# SCH_HDMI_GPIO.net
KiCad netlist of a schematic drawn in Altium Designer
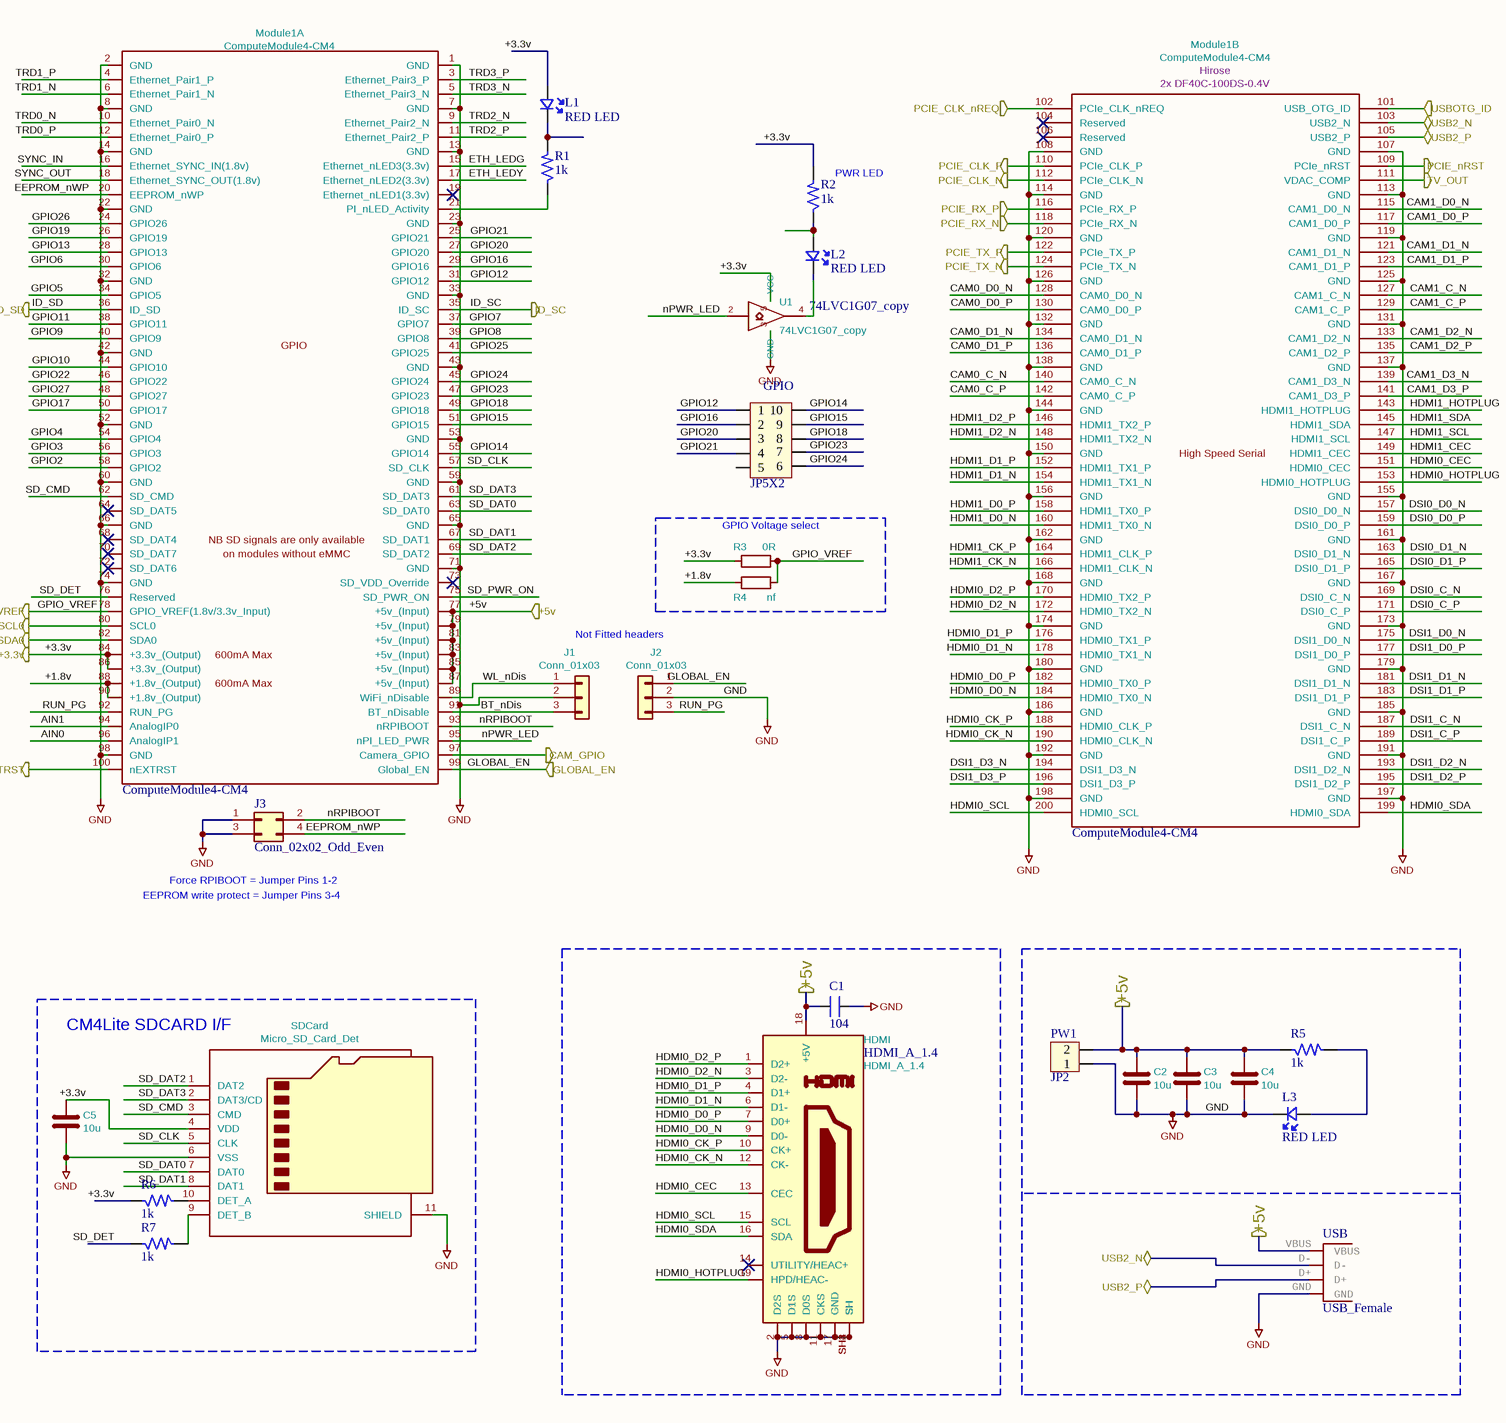
[diagram p0: SCH_HDMI_GPIO.SchDoc]

(export (version "E")
  (design (tool "Eeschema 10.0.6"))
  (components
    (comp (ref "C1")
      (value "104")
      (footprint "SM-CAP-0805")
      (fields (field (name "DESIGNED BY") "VanDungEvn"))
      (libsource (lib "QD_Lib_Altum") (part "CN"))
    )
    (comp (ref "C2") (value "10u") (footprint "C_0805_2012Metric") (libsource (lib "Device") (part "C")))
    (comp (ref "C3") (value "10u") (footprint "C_0805_2012Metric") (libsource (lib "Device") (part "C")))
    (comp (ref "C4") (value "10u") (footprint "C_0805_2012Metric") (libsource (lib "Device") (part "C")))
    (comp (ref "C5") (value "10u") (footprint "C_0805_2012Metric") (libsource (lib "Device") (part "C")))
    (comp (ref "GPIO") (value "JP5X2") (footprint "JP5X2") (libsource (lib "QD_Lib_Altum") (part "JP5X2")))
    (comp (ref "HDMI")
      (value "HDMI_A_1.4")
      (footprint "HDMI")
      (fields (field (name "ALTIUM_VALUE") "HDMI_A_1.4"))
      (libsource (lib "CM4IO") (part "HDMI_A_1.4"))
    )
    (comp (ref "J1")
      (value "Conn_01x03")
      (footprint "PinHeader_1x03_P2.54mm_Vertical")
      (libsource (lib "Connector_Generic") (part "Conn_01x03"))
    )
    (comp (ref "J2")
      (value "Conn_01x03")
      (footprint "PinHeader_1x03_P2.54mm_Vertical")
      (libsource (lib "") (part "Conn_01x03_1"))
    )
    (comp (ref "J3")
      (value "Conn_02x02_Odd_Even")
      (footprint "CON2x2")
      (libsource (lib "CM4_GPIO") (part "Conn_02x02_Odd_Even"))
    )
    (comp (ref "L1")
      (value "RED LED")
      (footprint "LED_0805")
      (description "Red 621nm LED Indication - Discrete 2V 0805 (2012 Metric)")
      (fields
        (field (name "MANUFACTURER") "Lite-On Inc.")
        (field (name "MANUFACTURER PART NUMBER") "LTST-C170EKT")
      )
      (libsource (lib "QD_Lib_Altum") (part "LED-RED_10mA-0805"))
    )
    (comp (ref "L2")
      (value "RED LED")
      (footprint "LED_0805")
      (description "Red 621nm LED Indication - Discrete 2V 0805 (2012 Metric)")
      (fields
        (field (name "MANUFACTURER") "Lite-On Inc.")
        (field (name "MANUFACTURER PART NUMBER") "LTST-C170EKT")
      )
      (libsource (lib "QD_Lib_Altum") (part "LED-RED_10mA-0805"))
    )
    (comp (ref "L3")
      (value "RED LED")
      (footprint "LED_0805")
      (description "Red 621nm LED Indication - Discrete 2V 0805 (2012 Metric)")
      (fields
        (field (name "MANUFACTURER") "Lite-On Inc.")
        (field (name "MANUFACTURER PART NUMBER") "LTST-C170EKT")
      )
      (libsource (lib "QD_Lib_Altum") (part "LED-RED_10mA-0805"))
    )
    (comp (ref "Module1")
      (value "ComputeModule4-CM4")
      (footprint "Raspberry-Pi-4-Compute-Module")
      (fields
        (field (name "ALTIUM_VALUE") "ComputeModule4-CM4")
        (field (name "FIELD4") "Hirose")
        (field (name "FIELD5") "2x DF40C-100DS-0.4V")
      )
      (libsource (lib "CM4IO") (part "ComputeModule4-CM4"))
    )
    (comp (ref "PW1")
      (value "JP2")
      (footprint "CON2")
      (description "Connector 2")
      (libsource (lib "QD_Lib_Altum") (part "Con2"))
    )
    (comp (ref "R1")
      (value "1k")
      (footprint "SM-RES-1206")
      (description "Resistor 1/4W")
      (libsource (lib "QD_Lib_Altum") (part "R"))
    )
    (comp (ref "R2")
      (value "1k")
      (footprint "SM-RES-1206")
      (description "Resistor 1/4W")
      (libsource (lib "QD_Lib_Altum") (part "R"))
    )
    (comp (ref "R3")
      (value "0R")
      (footprint "R_0805_2012Metric_Pad1.15x1.40mm_HandSolder")
      (libsource (lib "Device") (part "R"))
    )
    (comp (ref "R4")
      (value "nf")
      (footprint "R_0805_2012Metric_Pad1.15x1.40mm_HandSolder")
      (libsource (lib "Device") (part "R"))
    )
    (comp (ref "R5")
      (value "1k")
      (footprint "SM-RES-1206")
      (description "Resistor 1/4W")
      (libsource (lib "QD_Lib_Altum") (part "R"))
    )
    (comp (ref "R6")
      (value "1k")
      (footprint "SM-RES-1206")
      (description "Resistor 1/4W")
      (libsource (lib "QD_Lib_Altum") (part "R"))
    )
    (comp (ref "R7")
      (value "1k")
      (footprint "SM-RES-1206")
      (description "Resistor 1/4W")
      (libsource (lib "QD_Lib_Altum") (part "R"))
    )
    (comp (ref "SDCard")
      (value "Micro_SD_Card_Det")
      (footprint "SDCARD_MOLEX_503398-1892")
      (libsource (lib "Connector") (part "Micro_SD_Card_Det"))
    )
    (comp (ref "U1")
      (value "74LVC1G07_copy")
      (footprint "SOT-353_SC-70-5")
      (fields (field (name "ALTIUM_VALUE") "74LVC1G07_copy"))
      (libsource (lib "CM4IO") (part "74LVC1G07_copy"))
    )
    (comp (ref "USB")
      (value "USB_Female")
      (footprint "USB_Female")
      (libsource (lib "USB2-HUB") (part "USB_Female"))
    )
  )
  (nets
    (net (code "1") (name "/+1.8v") (class "Default")
      (node (ref "Module1") (pin "88") (pinfunction "+1.8v_(Output)_88") (pintype "passive"))
      (node (ref "Module1") (pin "90") (pinfunction "+1.8v_(Output)_90") (pintype "passive"))
      (node (ref "R4") (pin "1") (pinfunction "1_1") (pintype "passive"))
    )
    (net (code "2") (name "/+3.3v") (class "Default")
      (node (ref "C5") (pin "1") (pinfunction "1_1") (pintype "passive"))
      (node (ref "L1") (pin "A") (pinfunction "A_A") (pintype "passive"))
      (node (ref "Module1") (pin "84") (pinfunction "+3.3v_(Output)_84") (pintype "passive"))
      (node (ref "Module1") (pin "86") (pinfunction "+3.3v_(Output)_86") (pintype "passive"))
      (node (ref "R2") (pin "2") (pinfunction "2_2") (pintype "passive"))
      (node (ref "R3") (pin "1") (pinfunction "1_1") (pintype "passive"))
      (node (ref "R6") (pin "1") (pinfunction "1_1") (pintype "passive"))
      (node (ref "SDCard") (pin "4") (pinfunction "VDD_4") (pintype "passive"))
      (node (ref "U1") (pin "5") (pinfunction "VCC_5") (pintype "passive"))
    )
    (net (code "3") (name "/+5v") (class "Default")
      (node (ref "C1") (pin "1") (pinfunction "1_1") (pintype "passive"))
      (node (ref "C2") (pin "1") (pinfunction "1_1") (pintype "passive"))
      (node (ref "C3") (pin "1") (pinfunction "1_1") (pintype "passive"))
      (node (ref "C4") (pin "1") (pinfunction "1_1") (pintype "passive"))
      (node (ref "HDMI") (pin "18") (pinfunction "+5V_18") (pintype "passive"))
      (node (ref "Module1") (pin "77") (pinfunction "+5v_(Input)_77") (pintype "passive"))
      (node (ref "Module1") (pin "79") (pinfunction "+5v_(Input)_79") (pintype "passive"))
      (node (ref "Module1") (pin "81") (pinfunction "+5v_(Input)_81") (pintype "passive"))
      (node (ref "Module1") (pin "83") (pinfunction "+5v_(Input)_83") (pintype "passive"))
      (node (ref "Module1") (pin "85") (pinfunction "+5v_(Input)_85") (pintype "passive"))
      (node (ref "Module1") (pin "87") (pinfunction "+5v_(Input)_87") (pintype "passive"))
      (node (ref "PW1") (pin "2") (pinfunction "2_2") (pintype "passive"))
      (node (ref "R5") (pin "1") (pinfunction "1_1") (pintype "passive"))
      (node (ref "USB") (pin "VBUS") (pinfunction "VBUS_VBUS") (pintype "bidirectional"))
    )
    (net (code "4") (name "/AIN0") (class "Default")
      (node (ref "Module1") (pin "96") (pinfunction "AnalogIP1_96") (pintype "passive"))
    )
    (net (code "5") (name "/AIN1") (class "Default")
      (node (ref "Module1") (pin "94") (pinfunction "AnalogIP0_94") (pintype "passive"))
    )
    (net (code "6") (name "/BT_nDis") (class "Default")
      (node (ref "J1") (pin "3") (pinfunction "Pin_3_3") (pintype "passive"))
      (node (ref "Module1") (pin "91") (pinfunction "BT_nDisable_91") (pintype "passive"))
    )
    (net (code "7") (name "/CAM0_C_N") (class "Default")
      (node (ref "Module1") (pin "140") (pinfunction "CAM0_C_N_140") (pintype "passive"))
    )
    (net (code "8") (name "/CAM0_C_P") (class "Default")
      (node (ref "Module1") (pin "142") (pinfunction "CAM0_C_P_142") (pintype "passive"))
    )
    (net (code "9") (name "/CAM0_D0_N") (class "Default")
      (node (ref "Module1") (pin "128") (pinfunction "CAM0_D0_N_128") (pintype "passive"))
    )
    (net (code "10") (name "/CAM0_D0_P") (class "Default")
      (node (ref "Module1") (pin "130") (pinfunction "CAM0_D0_P_130") (pintype "passive"))
    )
    (net (code "11") (name "/CAM0_D1_N") (class "Default")
      (node (ref "Module1") (pin "134") (pinfunction "CAM0_D1_N_134") (pintype "passive"))
    )
    (net (code "12") (name "/CAM0_D1_P") (class "Default")
      (node (ref "Module1") (pin "136") (pinfunction "CAM0_D1_P_136") (pintype "passive"))
    )
    (net (code "13") (name "/CAM1_C_N") (class "Default")
      (node (ref "Module1") (pin "127") (pinfunction "CAM1_C_N_127") (pintype "passive"))
    )
    (net (code "14") (name "/CAM1_C_P") (class "Default")
      (node (ref "Module1") (pin "129") (pinfunction "CAM1_C_P_129") (pintype "passive"))
    )
    (net (code "15") (name "/CAM1_D0_N") (class "Default")
      (node (ref "Module1") (pin "115") (pinfunction "CAM1_D0_N_115") (pintype "passive"))
    )
    (net (code "16") (name "/CAM1_D0_P") (class "Default")
      (node (ref "Module1") (pin "117") (pinfunction "CAM1_D0_P_117") (pintype "passive"))
    )
    (net (code "17") (name "/CAM1_D1_N") (class "Default")
      (node (ref "Module1") (pin "121") (pinfunction "CAM1_D1_N_121") (pintype "passive"))
    )
    (net (code "18") (name "/CAM1_D1_P") (class "Default")
      (node (ref "Module1") (pin "123") (pinfunction "CAM1_D1_P_123") (pintype "passive"))
    )
    (net (code "19") (name "/CAM1_D2_N") (class "Default")
      (node (ref "Module1") (pin "133") (pinfunction "CAM1_D2_N_133") (pintype "passive"))
    )
    (net (code "20") (name "/CAM1_D2_P") (class "Default")
      (node (ref "Module1") (pin "135") (pinfunction "CAM1_D2_P_135") (pintype "passive"))
    )
    (net (code "21") (name "/CAM1_D3_N") (class "Default")
      (node (ref "Module1") (pin "139") (pinfunction "CAM1_D3_N_139") (pintype "passive"))
    )
    (net (code "22") (name "/CAM1_D3_P") (class "Default")
      (node (ref "Module1") (pin "141") (pinfunction "CAM1_D3_P_141") (pintype "passive"))
    )
    (net (code "23") (name "/CAM_GPIO") (class "Default")
      (node (ref "Module1") (pin "97") (pinfunction "Camera_GPIO_97") (pintype "passive"))
    )
    (net (code "24") (name "/DSI0_C_N") (class "Default")
      (node (ref "Module1") (pin "169") (pinfunction "DSI0_C_N_169") (pintype "passive"))
    )
    (net (code "25") (name "/DSI0_C_P") (class "Default")
      (node (ref "Module1") (pin "171") (pinfunction "DSI0_C_P_171") (pintype "passive"))
    )
    (net (code "26") (name "/DSI0_D0_N") (class "Default")
      (node (ref "Module1") (pin "157") (pinfunction "DSI0_D0_N_157") (pintype "passive"))
    )
    (net (code "27") (name "/DSI0_D0_P") (class "Default")
      (node (ref "Module1") (pin "159") (pinfunction "DSI0_D0_P_159") (pintype "passive"))
    )
    (net (code "28") (name "/DSI0_D1_N") (class "Default")
      (node (ref "Module1") (pin "163") (pinfunction "DSI0_D1_N_163") (pintype "passive"))
    )
    (net (code "29") (name "/DSI0_D1_P") (class "Default")
      (node (ref "Module1") (pin "165") (pinfunction "DSI0_D1_P_165") (pintype "passive"))
    )
    (net (code "30") (name "/DSI1_C_N") (class "Default")
      (node (ref "Module1") (pin "187") (pinfunction "DSI1_C_N_187") (pintype "passive"))
    )
    (net (code "31") (name "/DSI1_C_P") (class "Default")
      (node (ref "Module1") (pin "189") (pinfunction "DSI1_C_P_189") (pintype "passive"))
    )
    (net (code "32") (name "/DSI1_D0_N") (class "Default")
      (node (ref "Module1") (pin "175") (pinfunction "DSI1_D0_N_175") (pintype "passive"))
    )
    (net (code "33") (name "/DSI1_D0_P") (class "Default")
      (node (ref "Module1") (pin "177") (pinfunction "DSI1_D0_P_177") (pintype "passive"))
    )
    (net (code "34") (name "/DSI1_D1_N") (class "Default")
      (node (ref "Module1") (pin "181") (pinfunction "DSI1_D1_N_181") (pintype "passive"))
    )
    (net (code "35") (name "/DSI1_D1_P") (class "Default")
      (node (ref "Module1") (pin "183") (pinfunction "DSI1_D1_P_183") (pintype "passive"))
    )
    (net (code "36") (name "/DSI1_D2_N") (class "Default")
      (node (ref "Module1") (pin "193") (pinfunction "DSI1_D2_N_193") (pintype "passive"))
    )
    (net (code "37") (name "/DSI1_D2_P") (class "Default")
      (node (ref "Module1") (pin "195") (pinfunction "DSI1_D2_P_195") (pintype "passive"))
    )
    (net (code "38") (name "/DSI1_D3_N") (class "Default")
      (node (ref "Module1") (pin "194") (pinfunction "DSI1_D3_N_194") (pintype "passive"))
    )
    (net (code "39") (name "/DSI1_D3_P") (class "Default")
      (node (ref "Module1") (pin "196") (pinfunction "DSI1_D3_P_196") (pintype "passive"))
    )
    (net (code "40") (name "/EEPROM_nWP") (class "Default")
      (node (ref "J3") (pin "4") (pinfunction "Pin_4_4") (pintype "passive"))
      (node (ref "Module1") (pin "20") (pinfunction "EEPROM_nWP_20") (pintype "passive"))
    )
    (net (code "41") (name "/ETH_LEDG") (class "Default")
      (node (ref "Module1") (pin "15") (pinfunction "Ethernet_nLED3(3.3v)_15") (pintype "passive"))
    )
    (net (code "42") (name "/ETH_LEDY") (class "Default")
      (node (ref "Module1") (pin "17") (pinfunction "Ethernet_nLED2(3.3v)_17") (pintype "passive"))
    )
    (net (code "43") (name "/GLOBAL_EN") (class "Default")
      (node (ref "J2") (pin "1") (pinfunction "Pin_1_1") (pintype "passive"))
      (node (ref "Module1") (pin "99") (pinfunction "Global_EN_99") (pintype "passive"))
    )
    (net (code "44") (name "/GPIO2") (class "Default")
      (node (ref "Module1") (pin "58") (pinfunction "GPIO2_58") (pintype "passive"))
    )
    (net (code "45") (name "/GPIO3") (class "Default")
      (node (ref "Module1") (pin "56") (pinfunction "GPIO3_56") (pintype "passive"))
    )
    (net (code "46") (name "/GPIO4") (class "Default")
      (node (ref "Module1") (pin "54") (pinfunction "GPIO4_54") (pintype "passive"))
    )
    (net (code "47") (name "/GPIO5") (class "Default")
      (node (ref "Module1") (pin "34") (pinfunction "GPIO5_34") (pintype "passive"))
    )
    (net (code "48") (name "/GPIO6") (class "Default")
      (node (ref "Module1") (pin "30") (pinfunction "GPIO6_30") (pintype "passive"))
    )
    (net (code "49") (name "/GPIO7") (class "Default")
      (node (ref "Module1") (pin "37") (pinfunction "GPIO7_37") (pintype "passive"))
    )
    (net (code "50") (name "/GPIO8") (class "Default")
      (node (ref "Module1") (pin "39") (pinfunction "GPIO8_39") (pintype "passive"))
    )
    (net (code "51") (name "/GPIO9") (class "Default")
      (node (ref "Module1") (pin "40") (pinfunction "GPIO9_40") (pintype "passive"))
    )
    (net (code "52") (name "/GPIO10") (class "Default")
      (node (ref "Module1") (pin "44") (pinfunction "GPIO10_44") (pintype "passive"))
    )
    (net (code "53") (name "/GPIO11") (class "Default")
      (node (ref "Module1") (pin "38") (pinfunction "GPIO11_38") (pintype "passive"))
    )
    (net (code "54") (name "/GPIO12") (class "Default")
      (node (ref "GPIO") (pin "1") (pinfunction "1_1") (pintype "passive"))
      (node (ref "Module1") (pin "31") (pinfunction "GPIO12_31") (pintype "passive"))
    )
    (net (code "55") (name "/GPIO13") (class "Default")
      (node (ref "Module1") (pin "28") (pinfunction "GPIO13_28") (pintype "passive"))
    )
    (net (code "56") (name "/GPIO14") (class "Default")
      (node (ref "GPIO") (pin "10") (pinfunction "10_10") (pintype "passive"))
      (node (ref "Module1") (pin "55") (pinfunction "GPIO14_55") (pintype "passive"))
    )
    (net (code "57") (name "/GPIO15") (class "Default")
      (node (ref "GPIO") (pin "9") (pinfunction "9_9") (pintype "passive"))
      (node (ref "Module1") (pin "51") (pinfunction "GPIO15_51") (pintype "passive"))
    )
    (net (code "58") (name "/GPIO16") (class "Default")
      (node (ref "GPIO") (pin "2") (pinfunction "2_2") (pintype "passive"))
      (node (ref "Module1") (pin "29") (pinfunction "GPIO16_29") (pintype "passive"))
    )
    (net (code "59") (name "/GPIO17") (class "Default")
      (node (ref "Module1") (pin "50") (pinfunction "GPIO17_50") (pintype "passive"))
    )
    (net (code "60") (name "/GPIO18") (class "Default")
      (node (ref "GPIO") (pin "8") (pinfunction "8_8") (pintype "passive"))
      (node (ref "Module1") (pin "49") (pinfunction "GPIO18_49") (pintype "passive"))
    )
    (net (code "61") (name "/GPIO19") (class "Default")
      (node (ref "Module1") (pin "26") (pinfunction "GPIO19_26") (pintype "passive"))
    )
    (net (code "62") (name "/GPIO20") (class "Default")
      (node (ref "GPIO") (pin "3") (pinfunction "3_3") (pintype "passive"))
      (node (ref "Module1") (pin "27") (pinfunction "GPIO20_27") (pintype "passive"))
    )
    (net (code "63") (name "/GPIO21") (class "Default")
      (node (ref "GPIO") (pin "4") (pinfunction "4_4") (pintype "passive"))
      (node (ref "Module1") (pin "25") (pinfunction "GPIO21_25") (pintype "passive"))
    )
    (net (code "64") (name "/GPIO22") (class "Default")
      (node (ref "Module1") (pin "46") (pinfunction "GPIO22_46") (pintype "passive"))
    )
    (net (code "65") (name "/GPIO23") (class "Default")
      (node (ref "GPIO") (pin "7") (pinfunction "7_7") (pintype "passive"))
      (node (ref "Module1") (pin "47") (pinfunction "GPIO23_47") (pintype "passive"))
    )
    (net (code "66") (name "/GPIO24") (class "Default")
      (node (ref "GPIO") (pin "6") (pinfunction "6_6") (pintype "passive"))
      (node (ref "Module1") (pin "45") (pinfunction "GPIO24_45") (pintype "passive"))
    )
    (net (code "67") (name "/GPIO25") (class "Default")
      (node (ref "Module1") (pin "41") (pinfunction "GPIO25_41") (pintype "passive"))
    )
    (net (code "68") (name "/GPIO26") (class "Default")
      (node (ref "Module1") (pin "24") (pinfunction "GPIO26_24") (pintype "passive"))
    )
    (net (code "69") (name "/GPIO27") (class "Default")
      (node (ref "Module1") (pin "48") (pinfunction "GPIO27_48") (pintype "passive"))
    )
    (net (code "70") (name "/GPIO_VREF") (class "Default")
      (node (ref "Module1") (pin "78") (pinfunction "GPIO_VREF(1.8v/3.3v_Input)_78") (pintype "passive"))
      (node (ref "R3") (pin "2") (pinfunction "2_2") (pintype "passive"))
      (node (ref "R4") (pin "2") (pinfunction "2_2") (pintype "passive"))
    )
    (net (code "71") (name "/HDMI0_CEC") (class "Default")
      (node (ref "HDMI") (pin "13") (pinfunction "CEC_13") (pintype "passive"))
      (node (ref "Module1") (pin "151") (pinfunction "HDMI0_CEC_151") (pintype "passive"))
    )
    (net (code "72") (name "/HDMI0_CK_N") (class "Default")
      (node (ref "HDMI") (pin "12") (pinfunction "CK-_12") (pintype "passive"))
      (node (ref "Module1") (pin "190") (pinfunction "HDMI0_CLK_N_190") (pintype "passive"))
    )
    (net (code "73") (name "/HDMI0_CK_P") (class "Default")
      (node (ref "HDMI") (pin "10") (pinfunction "CK+_10") (pintype "passive"))
      (node (ref "Module1") (pin "188") (pinfunction "HDMI0_CLK_P_188") (pintype "passive"))
    )
    (net (code "74") (name "/HDMI0_D0_N") (class "Default")
      (node (ref "HDMI") (pin "9") (pinfunction "D0-_9") (pintype "passive"))
      (node (ref "Module1") (pin "184") (pinfunction "HDMI0_TX0_N_184") (pintype "passive"))
    )
    (net (code "75") (name "/HDMI0_D0_P") (class "Default")
      (node (ref "HDMI") (pin "7") (pinfunction "D0+_7") (pintype "passive"))
      (node (ref "Module1") (pin "182") (pinfunction "HDMI0_TX0_P_182") (pintype "passive"))
    )
    (net (code "76") (name "/HDMI0_D1_N") (class "Default")
      (node (ref "HDMI") (pin "6") (pinfunction "D1-_6") (pintype "passive"))
      (node (ref "Module1") (pin "178") (pinfunction "HDMI0_TX1_N_178") (pintype "passive"))
    )
    (net (code "77") (name "/HDMI0_D1_P") (class "Default")
      (node (ref "HDMI") (pin "4") (pinfunction "D1+_4") (pintype "passive"))
      (node (ref "Module1") (pin "176") (pinfunction "HDMI0_TX1_P_176") (pintype "passive"))
    )
    (net (code "78") (name "/HDMI0_D2_N") (class "Default")
      (node (ref "HDMI") (pin "3") (pinfunction "D2-_3") (pintype "passive"))
      (node (ref "Module1") (pin "172") (pinfunction "HDMI0_TX2_N_172") (pintype "passive"))
    )
    (net (code "79") (name "/HDMI0_D2_P") (class "Default")
      (node (ref "HDMI") (pin "1") (pinfunction "D2+_1") (pintype "passive"))
      (node (ref "Module1") (pin "170") (pinfunction "HDMI0_TX2_P_170") (pintype "passive"))
    )
    (net (code "80") (name "/HDMI0_HOTPLUG") (class "Default")
      (node (ref "HDMI") (pin "19") (pinfunction "HPD/HEAC-_19") (pintype "passive"))
      (node (ref "Module1") (pin "153") (pinfunction "HDMI0_HOTPLUG_153") (pintype "passive"))
    )
    (net (code "81") (name "/HDMI0_SCL") (class "Default")
      (node (ref "HDMI") (pin "15") (pinfunction "SCL_15") (pintype "passive"))
      (node (ref "Module1") (pin "200") (pinfunction "HDMI0_SCL_200") (pintype "passive"))
    )
    (net (code "82") (name "/HDMI0_SDA") (class "Default")
      (node (ref "HDMI") (pin "16") (pinfunction "SDA_16") (pintype "passive"))
      (node (ref "Module1") (pin "199") (pinfunction "HDMI0_SDA_199") (pintype "passive"))
    )
    (net (code "83") (name "/HDMI1_CEC") (class "Default")
      (node (ref "Module1") (pin "149") (pinfunction "HDMI1_CEC_149") (pintype "passive"))
    )
    (net (code "84") (name "/HDMI1_CK_N") (class "Default")
      (node (ref "Module1") (pin "166") (pinfunction "HDMI1_CLK_N_166") (pintype "passive"))
    )
    (net (code "85") (name "/HDMI1_CK_P") (class "Default")
      (node (ref "Module1") (pin "164") (pinfunction "HDMI1_CLK_P_164") (pintype "passive"))
    )
    (net (code "86") (name "/HDMI1_D0_N") (class "Default")
      (node (ref "Module1") (pin "160") (pinfunction "HDMI1_TX0_N_160") (pintype "passive"))
    )
    (net (code "87") (name "/HDMI1_D0_P") (class "Default")
      (node (ref "Module1") (pin "158") (pinfunction "HDMI1_TX0_P_158") (pintype "passive"))
    )
    (net (code "88") (name "/HDMI1_D1_N") (class "Default")
      (node (ref "Module1") (pin "154") (pinfunction "HDMI1_TX1_N_154") (pintype "passive"))
    )
    (net (code "89") (name "/HDMI1_D1_P") (class "Default")
      (node (ref "Module1") (pin "152") (pinfunction "HDMI1_TX1_P_152") (pintype "passive"))
    )
    (net (code "90") (name "/HDMI1_D2_N") (class "Default")
      (node (ref "Module1") (pin "148") (pinfunction "HDMI1_TX2_N_148") (pintype "passive"))
    )
    (net (code "91") (name "/HDMI1_D2_P") (class "Default")
      (node (ref "Module1") (pin "146") (pinfunction "HDMI1_TX2_P_146") (pintype "passive"))
    )
    (net (code "92") (name "/HDMI1_HOTPLUG") (class "Default")
      (node (ref "Module1") (pin "143") (pinfunction "HDMI1_HOTPLUG_143") (pintype "passive"))
    )
    (net (code "93") (name "/HDMI1_SCL") (class "Default")
      (node (ref "Module1") (pin "147") (pinfunction "HDMI1_SCL_147") (pintype "passive"))
    )
    (net (code "94") (name "/HDMI1_SDA") (class "Default")
      (node (ref "Module1") (pin "145") (pinfunction "HDMI1_SDA_145") (pintype "passive"))
    )
    (net (code "95") (name "/ID_SC") (class "Default")
      (node (ref "Module1") (pin "35") (pinfunction "ID_SC_35") (pintype "passive"))
    )
    (net (code "96") (name "/ID_SD") (class "Default")
      (node (ref "Module1") (pin "36") (pinfunction "ID_SD_36") (pintype "passive"))
    )
    (net (code "97") (name "/PCIE_CLK_N") (class "Default")
      (node (ref "Module1") (pin "112") (pinfunction "PCIe_CLK_N_112") (pintype "passive"))
    )
    (net (code "98") (name "/PCIE_CLK_P") (class "Default")
      (node (ref "Module1") (pin "110") (pinfunction "PCIe_CLK_P_110") (pintype "passive"))
    )
    (net (code "99") (name "/PCIE_CLK_nREQ") (class "Default")
      (node (ref "Module1") (pin "102") (pinfunction "PCIe_CLK_nREQ_102") (pintype "passive"))
    )
    (net (code "100") (name "/PCIE_RX_N") (class "Default")
      (node (ref "Module1") (pin "118") (pinfunction "PCIe_RX_N_118") (pintype "passive"))
    )
    (net (code "101") (name "/PCIE_RX_P") (class "Default")
      (node (ref "Module1") (pin "116") (pinfunction "PCIe_RX_P_116") (pintype "passive"))
    )
    (net (code "102") (name "/PCIE_TX_N") (class "Default")
      (node (ref "Module1") (pin "124") (pinfunction "PCIe_TX_N_124") (pintype "passive"))
    )
    (net (code "103") (name "/PCIE_TX_P") (class "Default")
      (node (ref "Module1") (pin "122") (pinfunction "PCIe_TX_P_122") (pintype "passive"))
    )
    (net (code "104") (name "/PCIE_nRST") (class "Default")
      (node (ref "Module1") (pin "109") (pinfunction "PCIe_nRST_109") (pintype "passive"))
    )
    (net (code "105") (name "/RUN_PG") (class "Default")
      (node (ref "J2") (pin "3") (pinfunction "Pin_3_3") (pintype "passive"))
      (node (ref "Module1") (pin "92") (pinfunction "RUN_PG_92") (pintype "passive"))
    )
    (net (code "106") (name "/SCL0") (class "Default")
      (node (ref "Module1") (pin "80") (pinfunction "SCL0_80") (pintype "passive"))
    )
    (net (code "107") (name "/SDA0") (class "Default")
      (node (ref "Module1") (pin "82") (pinfunction "SDA0_82") (pintype "passive"))
    )
    (net (code "108") (name "/SD_CLK") (class "Default")
      (node (ref "Module1") (pin "57") (pinfunction "SD_CLK_57") (pintype "passive"))
      (node (ref "SDCard") (pin "5") (pinfunction "CLK_5") (pintype "passive"))
    )
    (net (code "109") (name "/SD_CMD") (class "Default")
      (node (ref "Module1") (pin "62") (pinfunction "SD_CMD_62") (pintype "passive"))
      (node (ref "SDCard") (pin "3") (pinfunction "CMD_3") (pintype "passive"))
    )
    (net (code "110") (name "/SD_DAT0") (class "Default")
      (node (ref "Module1") (pin "63") (pinfunction "SD_DAT0_63") (pintype "passive"))
      (node (ref "SDCard") (pin "7") (pinfunction "DAT0_7") (pintype "passive"))
    )
    (net (code "111") (name "/SD_DAT1") (class "Default")
      (node (ref "Module1") (pin "67") (pinfunction "SD_DAT1_67") (pintype "passive"))
      (node (ref "SDCard") (pin "8") (pinfunction "DAT1_8") (pintype "passive"))
    )
    (net (code "112") (name "/SD_DAT2") (class "Default")
      (node (ref "Module1") (pin "69") (pinfunction "SD_DAT2_69") (pintype "passive"))
      (node (ref "SDCard") (pin "1") (pinfunction "DAT2_1") (pintype "passive"))
    )
    (net (code "113") (name "/SD_DAT3") (class "Default")
      (node (ref "Module1") (pin "61") (pinfunction "SD_DAT3_61") (pintype "passive"))
      (node (ref "SDCard") (pin "2") (pinfunction "DAT3/CD_2") (pintype "passive"))
    )
    (net (code "114") (name "/SD_DET") (class "Default")
      (node (ref "Module1") (pin "76") (pinfunction "Reserved_76") (pintype "passive"))
      (node (ref "R7") (pin "1") (pinfunction "1_1") (pintype "passive"))
    )
    (net (code "115") (name "/SD_PWR_ON") (class "Default")
      (node (ref "Module1") (pin "75") (pinfunction "SD_PWR_ON_75") (pintype "passive"))
    )
    (net (code "116") (name "/SYNC_IN") (class "Default")
      (node (ref "Module1") (pin "16") (pinfunction "Ethernet_SYNC_IN(1.8v)_16") (pintype "passive"))
    )
    (net (code "117") (name "/SYNC_OUT") (class "Default")
      (node (ref "Module1") (pin "18") (pinfunction "Ethernet_SYNC_OUT(1.8v)_18") (pintype "passive"))
    )
    (net (code "118") (name "/TRD0_N") (class "Default")
      (node (ref "Module1") (pin "10") (pinfunction "Ethernet_Pair0_N_10") (pintype "passive"))
    )
    (net (code "119") (name "/TRD0_P") (class "Default")
      (node (ref "Module1") (pin "12") (pinfunction "Ethernet_Pair0_P_12") (pintype "passive"))
    )
    (net (code "120") (name "/TRD1_N") (class "Default")
      (node (ref "Module1") (pin "6") (pinfunction "Ethernet_Pair1_N_6") (pintype "passive"))
    )
    (net (code "121") (name "/TRD1_P") (class "Default")
      (node (ref "Module1") (pin "4") (pinfunction "Ethernet_Pair1_P_4") (pintype "passive"))
    )
    (net (code "122") (name "/TRD2_N") (class "Default")
      (node (ref "Module1") (pin "9") (pinfunction "Ethernet_Pair2_N_9") (pintype "passive"))
    )
    (net (code "123") (name "/TRD2_P") (class "Default")
      (node (ref "Module1") (pin "11") (pinfunction "Ethernet_Pair2_P_11") (pintype "passive"))
    )
    (net (code "124") (name "/TRD3_N") (class "Default")
      (node (ref "Module1") (pin "5") (pinfunction "Ethernet_Pair3_N_5") (pintype "passive"))
    )
    (net (code "125") (name "/TRD3_P") (class "Default")
      (node (ref "Module1") (pin "3") (pinfunction "Ethernet_Pair3_P_3") (pintype "passive"))
    )
    (net (code "126") (name "/TV_OUT") (class "Default")
      (node (ref "Module1") (pin "111") (pinfunction "VDAC_COMP_111") (pintype "passive"))
    )
    (net (code "127") (name "/USB2_N") (class "Default")
      (node (ref "Module1") (pin "103") (pinfunction "USB2_N_103") (pintype "passive"))
      (node (ref "USB") (pin "D-") (pinfunction "D-_D-") (pintype "bidirectional"))
    )
    (net (code "128") (name "/USB2_P") (class "Default")
      (node (ref "Module1") (pin "105") (pinfunction "USB2_P_105") (pintype "passive"))
      (node (ref "USB") (pin "D+") (pinfunction "D+_D+") (pintype "bidirectional"))
    )
    (net (code "129") (name "/USBOTG_ID") (class "Default")
      (node (ref "Module1") (pin "101") (pinfunction "USB_OTG_ID_101") (pintype "passive"))
    )
    (net (code "130") (name "/WL_nDis") (class "Default")
      (node (ref "J1") (pin "1") (pinfunction "Pin_1_1") (pintype "passive"))
      (node (ref "Module1") (pin "89") (pinfunction "WiFi_nDisable_89") (pintype "passive"))
    )
    (net (code "131") (name "/nEXTRST") (class "Default")
      (node (ref "Module1") (pin "100") (pinfunction "nEXTRST_100") (pintype "passive"))
    )
    (net (code "132") (name "/nPWR_LED") (class "Default")
      (node (ref "Module1") (pin "95") (pinfunction "nPI_LED_PWR_95") (pintype "passive"))
      (node (ref "U1") (pin "2") (pinfunction "2_2") (pintype "passive"))
    )
    (net (code "133") (name "/nRPIBOOT") (class "Default")
      (node (ref "J3") (pin "2") (pinfunction "Pin_2_2") (pintype "passive"))
      (node (ref "Module1") (pin "93") (pinfunction "nRPIBOOT_93") (pintype "passive"))
    )
    (net (code "134") (name "GND") (class "Default")
      (node (ref "C1") (pin "2") (pinfunction "2_2") (pintype "passive"))
      (node (ref "C2") (pin "2") (pinfunction "2_2") (pintype "passive"))
      (node (ref "C3") (pin "2") (pinfunction "2_2") (pintype "passive"))
      (node (ref "C4") (pin "2") (pinfunction "2_2") (pintype "passive"))
      (node (ref "C5") (pin "2") (pinfunction "2_2") (pintype "passive"))
      (node (ref "HDMI") (pin "11") (pinfunction "CKS_11") (pintype "passive"))
      (node (ref "HDMI") (pin "17") (pinfunction "GND_17") (pintype "passive"))
      (node (ref "HDMI") (pin "2") (pinfunction "D2S_2") (pintype "passive"))
      (node (ref "HDMI") (pin "5") (pinfunction "D1S_5") (pintype "passive"))
      (node (ref "HDMI") (pin "8") (pinfunction "D0S_8") (pintype "passive"))
      (node (ref "HDMI") (pin "SH1") (pinfunction "SH_SH1") (pintype "passive"))
      (node (ref "HDMI") (pin "SH2") (pinfunction "SH_SH2") (pintype "passive"))
      (node (ref "HDMI") (pin "SH3") (pinfunction "SH_SH3") (pintype "passive"))
      (node (ref "HDMI") (pin "SH4") (pinfunction "SH_SH4") (pintype "passive"))
      (node (ref "J1") (pin "2") (pinfunction "Pin_2_2") (pintype "passive"))
      (node (ref "J2") (pin "2") (pinfunction "Pin_2_2") (pintype "passive"))
      (node (ref "J3") (pin "1") (pinfunction "Pin_1_1") (pintype "passive"))
      (node (ref "J3") (pin "3") (pinfunction "Pin_3_3") (pintype "passive"))
      (node (ref "L3") (pin "K") (pinfunction "K_K") (pintype "passive"))
      (node (ref "Module1") (pin "1") (pinfunction "GND_1") (pintype "passive"))
      (node (ref "Module1") (pin "107") (pinfunction "GND_107") (pintype "passive"))
      (node (ref "Module1") (pin "108") (pinfunction "GND_108") (pintype "passive"))
      (node (ref "Module1") (pin "113") (pinfunction "GND_113") (pintype "passive"))
      (node (ref "Module1") (pin "114") (pinfunction "GND_114") (pintype "passive"))
      (node (ref "Module1") (pin "119") (pinfunction "GND_119") (pintype "passive"))
      (node (ref "Module1") (pin "120") (pinfunction "GND_120") (pintype "passive"))
      (node (ref "Module1") (pin "125") (pinfunction "GND_125") (pintype "passive"))
      (node (ref "Module1") (pin "126") (pinfunction "GND_126") (pintype "passive"))
      (node (ref "Module1") (pin "13") (pinfunction "GND_13") (pintype "passive"))
      (node (ref "Module1") (pin "131") (pinfunction "GND_131") (pintype "passive"))
      (node (ref "Module1") (pin "132") (pinfunction "GND_132") (pintype "passive"))
      (node (ref "Module1") (pin "137") (pinfunction "GND_137") (pintype "passive"))
      (node (ref "Module1") (pin "138") (pinfunction "GND_138") (pintype "passive"))
      (node (ref "Module1") (pin "14") (pinfunction "GND_14") (pintype "passive"))
      (node (ref "Module1") (pin "144") (pinfunction "GND_144") (pintype "passive"))
      (node (ref "Module1") (pin "150") (pinfunction "GND_150") (pintype "passive"))
      (node (ref "Module1") (pin "155") (pinfunction "GND_155") (pintype "passive"))
      (node (ref "Module1") (pin "156") (pinfunction "GND_156") (pintype "passive"))
      (node (ref "Module1") (pin "161") (pinfunction "GND_161") (pintype "passive"))
      (node (ref "Module1") (pin "162") (pinfunction "GND_162") (pintype "passive"))
      (node (ref "Module1") (pin "167") (pinfunction "GND_167") (pintype "passive"))
      (node (ref "Module1") (pin "168") (pinfunction "GND_168") (pintype "passive"))
      (node (ref "Module1") (pin "173") (pinfunction "GND_173") (pintype "passive"))
      (node (ref "Module1") (pin "174") (pinfunction "GND_174") (pintype "passive"))
      (node (ref "Module1") (pin "179") (pinfunction "GND_179") (pintype "passive"))
      (node (ref "Module1") (pin "180") (pinfunction "GND_180") (pintype "passive"))
      (node (ref "Module1") (pin "185") (pinfunction "GND_185") (pintype "passive"))
      (node (ref "Module1") (pin "186") (pinfunction "GND_186") (pintype "passive"))
      (node (ref "Module1") (pin "191") (pinfunction "GND_191") (pintype "passive"))
      (node (ref "Module1") (pin "192") (pinfunction "GND_192") (pintype "passive"))
      (node (ref "Module1") (pin "197") (pinfunction "GND_197") (pintype "passive"))
      (node (ref "Module1") (pin "198") (pinfunction "GND_198") (pintype "passive"))
      (node (ref "Module1") (pin "2") (pinfunction "GND_2") (pintype "passive"))
      (node (ref "Module1") (pin "22") (pinfunction "GND_22") (pintype "passive"))
      (node (ref "Module1") (pin "23") (pinfunction "GND_23") (pintype "passive"))
      (node (ref "Module1") (pin "32") (pinfunction "GND_32") (pintype "passive"))
      (node (ref "Module1") (pin "33") (pinfunction "GND_33") (pintype "passive"))
      (node (ref "Module1") (pin "42") (pinfunction "GND_42") (pintype "passive"))
      (node (ref "Module1") (pin "43") (pinfunction "GND_43") (pintype "passive"))
      (node (ref "Module1") (pin "52") (pinfunction "GND_52") (pintype "passive"))
      (node (ref "Module1") (pin "53") (pinfunction "GND_53") (pintype "passive"))
      (node (ref "Module1") (pin "59") (pinfunction "GND_59") (pintype "passive"))
      (node (ref "Module1") (pin "60") (pinfunction "GND_60") (pintype "passive"))
      (node (ref "Module1") (pin "65") (pinfunction "GND_65") (pintype "passive"))
      (node (ref "Module1") (pin "66") (pinfunction "GND_66") (pintype "passive"))
      (node (ref "Module1") (pin "7") (pinfunction "GND_7") (pintype "passive"))
      (node (ref "Module1") (pin "71") (pinfunction "GND_71") (pintype "passive"))
      (node (ref "Module1") (pin "74") (pinfunction "GND_74") (pintype "passive"))
      (node (ref "Module1") (pin "8") (pinfunction "GND_8") (pintype "passive"))
      (node (ref "Module1") (pin "98") (pinfunction "GND_98") (pintype "passive"))
      (node (ref "PW1") (pin "1") (pinfunction "1_1") (pintype "passive"))
      (node (ref "SDCard") (pin "11") (pinfunction "SHIELD_11") (pintype "passive"))
      (node (ref "SDCard") (pin "6") (pinfunction "VSS_6") (pintype "passive"))
      (node (ref "U1") (pin "3") (pinfunction "GND_3") (pintype "passive"))
      (node (ref "USB") (pin "GND") (pinfunction "GND_GND") (pintype "bidirectional"))
    )
    (net (code "135") (name "Net-(L1-PadK)") (class "Default")
      (node (ref "L1") (pin "K") (pinfunction "K_K") (pintype "passive"))
      (node (ref "R1") (pin "2") (pinfunction "2_2") (pintype "passive"))
    )
    (net (code "136") (name "Net-(L2-PadA)") (class "Default")
      (node (ref "L2") (pin "A") (pinfunction "A_A") (pintype "passive"))
      (node (ref "R2") (pin "1") (pinfunction "1_1") (pintype "passive"))
    )
    (net (code "137") (name "Net-(L2-PadK)") (class "Default")
      (node (ref "L2") (pin "K") (pinfunction "K_K") (pintype "passive"))
      (node (ref "U1") (pin "4") (pinfunction "4_4") (pintype "passive"))
    )
    (net (code "138") (name "Net-(L3-PadA)") (class "Default")
      (node (ref "L3") (pin "A") (pinfunction "A_A") (pintype "passive"))
      (node (ref "R5") (pin "2") (pinfunction "2_2") (pintype "passive"))
    )
    (net (code "139") (name "Net-(Module1A-PI_nLED_Activity)") (class "Default")
      (node (ref "Module1") (pin "21") (pinfunction "PI_nLED_Activity_21") (pintype "passive"))
      (node (ref "R1") (pin "1") (pinfunction "1_1") (pintype "passive"))
    )
    (net (code "140") (name "Net-(SDCard-DET_A)") (class "Default")
      (node (ref "R6") (pin "2") (pinfunction "2_2") (pintype "passive"))
      (node (ref "SDCard") (pin "10") (pinfunction "DET_A_10") (pintype "passive"))
    )
    (net (code "141") (name "Net-(SDCard-DET_B)") (class "Default")
      (node (ref "R7") (pin "2") (pinfunction "2_2") (pintype "passive"))
      (node (ref "SDCard") (pin "9") (pinfunction "DET_B_9") (pintype "passive"))
    )
    (net (code "142") (name "unconnected-(GPIO-Pad5)") (class "Default")
      (node (ref "GPIO") (pin "5") (pinfunction "5_5") (pintype "passive"))
    )
    (net (code "143") (name "unconnected-(HDMI-UTILITY{slash}HEAC+-Pad14)") (class "Default")
      (node (ref "HDMI") (pin "14") (pinfunction "UTILITY/HEAC+_14") (pintype "passive+no_connect"))
    )
    (net (code "144") (name "unconnected-(Module1A-Ethernet_nLED1(3.3v)-Pad19)") (class "Default")
      (node (ref "Module1") (pin "19") (pinfunction "Ethernet_nLED1(3.3v)_19") (pintype "passive+no_connect"))
    )
    (net (code "145") (name "unconnected-(Module1A-SD_DAT4-Pad68)") (class "Default")
      (node (ref "Module1") (pin "68") (pinfunction "SD_DAT4_68") (pintype "passive+no_connect"))
    )
    (net (code "146") (name "unconnected-(Module1A-SD_DAT5-Pad64)") (class "Default")
      (node (ref "Module1") (pin "64") (pinfunction "SD_DAT5_64") (pintype "passive+no_connect"))
    )
    (net (code "147") (name "unconnected-(Module1A-SD_DAT6-Pad72)") (class "Default")
      (node (ref "Module1") (pin "72") (pinfunction "SD_DAT6_72") (pintype "passive+no_connect"))
    )
    (net (code "148") (name "unconnected-(Module1A-SD_DAT7-Pad70)") (class "Default")
      (node (ref "Module1") (pin "70") (pinfunction "SD_DAT7_70") (pintype "passive+no_connect"))
    )
    (net (code "149") (name "unconnected-(Module1A-SD_VDD_Override-Pad73)") (class "Default")
      (node (ref "Module1") (pin "73") (pinfunction "SD_VDD_Override_73") (pintype "passive+no_connect"))
    )
    (net (code "150") (name "unconnected-(Module1B-Reserved-Pad104)") (class "Default")
      (node (ref "Module1") (pin "104") (pinfunction "Reserved_104") (pintype "passive+no_connect"))
    )
    (net (code "151") (name "unconnected-(Module1B-Reserved-Pad106)") (class "Default")
      (node (ref "Module1") (pin "106") (pinfunction "Reserved_106") (pintype "passive+no_connect"))
    )
  )
)
